# Editable_Schematic_File.net
KiCad netlist of a schematic drawn in EasyEDA
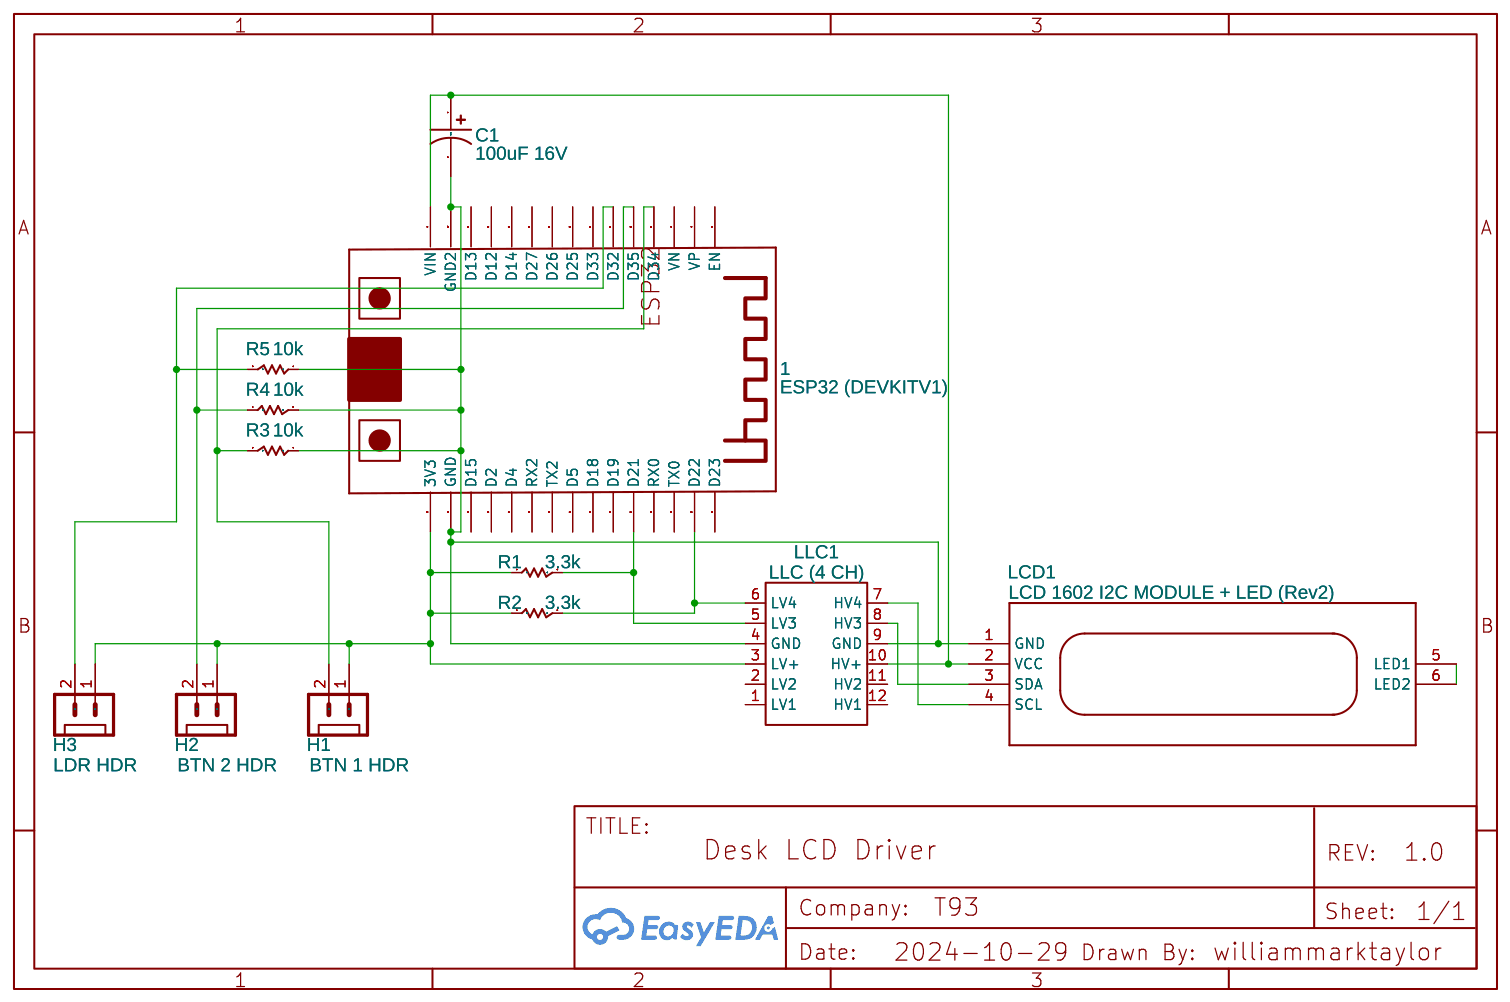
[diagram p0: schematic sheet]

(export (version "E")
  (design (tool "Eeschema 10.0.6"))
  (components
    (comp (ref "1") (value "ESP32 (DEVKITV1)") (libsource (lib "") (part "ESP32-DEVKIT-V1-30PIN")))
    (comp (ref "C1") (value "100uF 16V") (libsource (lib "") (part "CE_TH_D5.0×F2.0_US")))
    (comp (ref "H1") (value "BTN 1 HDR") (libsource (lib "") (part "2PIN-HEADER-2.54")))
    (comp (ref "H2") (value "BTN 2 HDR") (libsource (lib "") (part "2PIN-HEADER-2.54")))
    (comp (ref "H3") (value "LDR HDR") (libsource (lib "") (part "2PIN-HEADER-2.54")))
    (comp (ref "LCD1")
      (value "LCD 1602 I2C MODULE + LED (Rev2)")
      (libsource (lib "") (part "LCD 1602 I2C MODULE + LED (Rev2)"))
    )
    (comp (ref "LLC1") (value "LLC (4 CH)") (libsource (lib "") (part "Logic-Level Converter (4CH)")))
    (comp (ref "R1") (value "3.3k") (libsource (lib "") (part "R_AXIAL-0.3_US-minified-sch_1")))
    (comp (ref "R2") (value "3.3k") (libsource (lib "") (part "R_AXIAL-0.3_US-minified-sch_1")))
    (comp (ref "R3") (value "10k") (libsource (lib "") (part "R_AXIAL-0.3_US-minified-sch")))
    (comp (ref "R4") (value "10k") (libsource (lib "") (part "R_AXIAL-0.3_US-minified-sch_1")))
    (comp (ref "R5") (value "10k") (libsource (lib "") (part "R_AXIAL-0.3_US-minified-sch")))
  )
  (nets
    (net (code "1") (name "Net-(1-PadD32)") (class "Default")
      (node (ref "1") (pin "D32") (pinfunction "D32_D32") (pintype "unspecified"))
      (node (ref "H3") (pin "2") (pinfunction "2_2") (pintype "unspecified"))
      (node (ref "R5") (pin "2") (pinfunction "2_2") (pintype "unspecified"))
    )
    (net (code "2") (name "Net-(1-PadD34)") (class "Default")
      (node (ref "1") (pin "D34") (pinfunction "D34_D34") (pintype "unspecified"))
      (node (ref "H1") (pin "2") (pinfunction "2_2") (pintype "unspecified"))
      (node (ref "R3") (pin "2") (pinfunction "2_2") (pintype "unspecified"))
    )
    (net (code "3") (name "Net-(1-PadD35)") (class "Default")
      (node (ref "1") (pin "D35") (pinfunction "D35_D35") (pintype "unspecified"))
      (node (ref "H2") (pin "2") (pinfunction "2_2") (pintype "unspecified"))
      (node (ref "R4") (pin "1") (pinfunction "1_1") (pintype "unspecified"))
    )
    (net (code "4") (name "Net-(LCD1-GND)") (class "Default")
      (node (ref "1") (pin "GND") (pinfunction "GND_GND") (pintype "unspecified"))
      (node (ref "1") (pin "GND2") (pinfunction "GND2_GND2") (pintype "unspecified"))
      (node (ref "C1") (pin "2") (pinfunction "2_2") (pintype "unspecified"))
      (node (ref "LCD1") (pin "1") (pinfunction "GND_1") (pintype "unspecified"))
      (node (ref "LLC1") (pin "4") (pinfunction "GND_4") (pintype "unspecified"))
      (node (ref "LLC1") (pin "9") (pinfunction "GND_9") (pintype "unspecified"))
      (node (ref "R3") (pin "1") (pinfunction "1_1") (pintype "unspecified"))
      (node (ref "R4") (pin "2") (pinfunction "2_2") (pintype "unspecified"))
      (node (ref "R5") (pin "1") (pinfunction "1_1") (pintype "unspecified"))
    )
    (net (code "5") (name "Net-(LCD1-LED1)") (class "Default")
      (node (ref "LCD1") (pin "5") (pinfunction "LED1_5") (pintype "unspecified"))
      (node (ref "LCD1") (pin "6") (pinfunction "LED2_6") (pintype "unspecified"))
    )
    (net (code "6") (name "Net-(LCD1-SCL)") (class "Default")
      (node (ref "LCD1") (pin "4") (pinfunction "SCL_4") (pintype "unspecified"))
      (node (ref "LLC1") (pin "7") (pinfunction "HV4_7") (pintype "unspecified"))
    )
    (net (code "7") (name "Net-(LCD1-SDA)") (class "Default")
      (node (ref "LCD1") (pin "3") (pinfunction "SDA_3") (pintype "unspecified"))
      (node (ref "LLC1") (pin "8") (pinfunction "HV3_8") (pintype "unspecified"))
    )
    (net (code "8") (name "Net-(LCD1-VCC)") (class "Default")
      (node (ref "1") (pin "VIN") (pinfunction "VIN_VIN") (pintype "unspecified"))
      (node (ref "C1") (pin "1") (pinfunction "1_1") (pintype "unspecified"))
      (node (ref "LCD1") (pin "2") (pinfunction "VCC_2") (pintype "unspecified"))
      (node (ref "LLC1") (pin "10") (pinfunction "HV+_10") (pintype "unspecified"))
    )
    (net (code "9") (name "Net-(LLC1-LV+)") (class "Default")
      (node (ref "1") (pin "3V3") (pinfunction "3V3_3V3") (pintype "unspecified"))
      (node (ref "H1") (pin "1") (pinfunction "1_1") (pintype "unspecified"))
      (node (ref "H2") (pin "1") (pinfunction "1_1") (pintype "unspecified"))
      (node (ref "H3") (pin "1") (pinfunction "1_1") (pintype "unspecified"))
      (node (ref "LLC1") (pin "3") (pinfunction "LV+_3") (pintype "unspecified"))
      (node (ref "R1") (pin "1") (pinfunction "1_1") (pintype "unspecified"))
      (node (ref "R2") (pin "1") (pinfunction "1_1") (pintype "unspecified"))
    )
    (net (code "10") (name "Net-(LLC1-LV3)") (class "Default")
      (node (ref "1") (pin "D21") (pinfunction "D21_D21") (pintype "unspecified"))
      (node (ref "LLC1") (pin "5") (pinfunction "LV3_5") (pintype "unspecified"))
      (node (ref "R1") (pin "2") (pinfunction "2_2") (pintype "unspecified"))
    )
    (net (code "11") (name "Net-(LLC1-LV4)") (class "Default")
      (node (ref "1") (pin "D22") (pinfunction "D22_D22") (pintype "unspecified"))
      (node (ref "LLC1") (pin "6") (pinfunction "LV4_6") (pintype "unspecified"))
      (node (ref "R2") (pin "2") (pinfunction "2_2") (pintype "unspecified"))
    )
    (net (code "12") (name "unconnected-(1-PadD2)") (class "Default")
      (node (ref "1") (pin "D2") (pinfunction "D2_D2") (pintype "unspecified"))
    )
    (net (code "13") (name "unconnected-(1-PadD4)") (class "Default")
      (node (ref "1") (pin "D4") (pinfunction "D4_D4") (pintype "unspecified"))
    )
    (net (code "14") (name "unconnected-(1-PadD5)") (class "Default")
      (node (ref "1") (pin "D5") (pinfunction "D5_D5") (pintype "unspecified"))
    )
    (net (code "15") (name "unconnected-(1-PadD12)") (class "Default")
      (node (ref "1") (pin "D12") (pinfunction "D12_D12") (pintype "unspecified"))
    )
    (net (code "16") (name "unconnected-(1-PadD13)") (class "Default")
      (node (ref "1") (pin "D13") (pinfunction "D13_D13") (pintype "unspecified"))
    )
    (net (code "17") (name "unconnected-(1-PadD14)") (class "Default")
      (node (ref "1") (pin "D14") (pinfunction "D14_D14") (pintype "unspecified"))
    )
    (net (code "18") (name "unconnected-(1-PadD15)") (class "Default")
      (node (ref "1") (pin "D15") (pinfunction "D15_D15") (pintype "unspecified"))
    )
    (net (code "19") (name "unconnected-(1-PadD18)") (class "Default")
      (node (ref "1") (pin "D18") (pinfunction "D18_D18") (pintype "unspecified"))
    )
    (net (code "20") (name "unconnected-(1-PadD19)") (class "Default")
      (node (ref "1") (pin "D19") (pinfunction "D19_D19") (pintype "unspecified"))
    )
    (net (code "21") (name "unconnected-(1-PadD23)") (class "Default")
      (node (ref "1") (pin "D23") (pinfunction "D23_D23") (pintype "unspecified"))
    )
    (net (code "22") (name "unconnected-(1-PadD25)") (class "Default")
      (node (ref "1") (pin "D25") (pinfunction "D25_D25") (pintype "unspecified"))
    )
    (net (code "23") (name "unconnected-(1-PadD26)") (class "Default")
      (node (ref "1") (pin "D26") (pinfunction "D26_D26") (pintype "unspecified"))
    )
    (net (code "24") (name "unconnected-(1-PadD27)") (class "Default")
      (node (ref "1") (pin "D27") (pinfunction "D27_D27") (pintype "unspecified"))
    )
    (net (code "25") (name "unconnected-(1-PadD33)") (class "Default")
      (node (ref "1") (pin "D33") (pinfunction "D33_D33") (pintype "unspecified"))
    )
    (net (code "26") (name "unconnected-(1-PadEN)") (class "Default")
      (node (ref "1") (pin "EN") (pinfunction "EN_EN") (pintype "unspecified"))
    )
    (net (code "27") (name "unconnected-(1-PadRX0)") (class "Default")
      (node (ref "1") (pin "RX0") (pinfunction "RX0_RX0") (pintype "unspecified"))
    )
    (net (code "28") (name "unconnected-(1-PadRX2)") (class "Default")
      (node (ref "1") (pin "RX2") (pinfunction "RX2_RX2") (pintype "unspecified"))
    )
    (net (code "29") (name "unconnected-(1-PadTX0)") (class "Default")
      (node (ref "1") (pin "TX0") (pinfunction "TX0_TX0") (pintype "unspecified"))
    )
    (net (code "30") (name "unconnected-(1-PadTX2)") (class "Default")
      (node (ref "1") (pin "TX2") (pinfunction "TX2_TX2") (pintype "unspecified"))
    )
    (net (code "31") (name "unconnected-(1-PadVN)") (class "Default")
      (node (ref "1") (pin "VN") (pinfunction "VN_VN") (pintype "unspecified"))
    )
    (net (code "32") (name "unconnected-(1-PadVP)") (class "Default")
      (node (ref "1") (pin "VP") (pinfunction "VP_VP") (pintype "unspecified"))
    )
    (net (code "33") (name "unconnected-(LLC1-HV1-Pad12)") (class "Default")
      (node (ref "LLC1") (pin "12") (pinfunction "HV1_12") (pintype "unspecified"))
    )
    (net (code "34") (name "unconnected-(LLC1-HV2-Pad11)") (class "Default")
      (node (ref "LLC1") (pin "11") (pinfunction "HV2_11") (pintype "unspecified"))
    )
    (net (code "35") (name "unconnected-(LLC1-LV1-Pad1)") (class "Default")
      (node (ref "LLC1") (pin "1") (pinfunction "LV1_1") (pintype "unspecified"))
    )
    (net (code "36") (name "unconnected-(LLC1-LV2-Pad2)") (class "Default")
      (node (ref "LLC1") (pin "2") (pinfunction "LV2_2") (pintype "unspecified"))
    )
  )
)
